# Sheet_1.net
KiCad netlist of a schematic drawn in Altium Designer
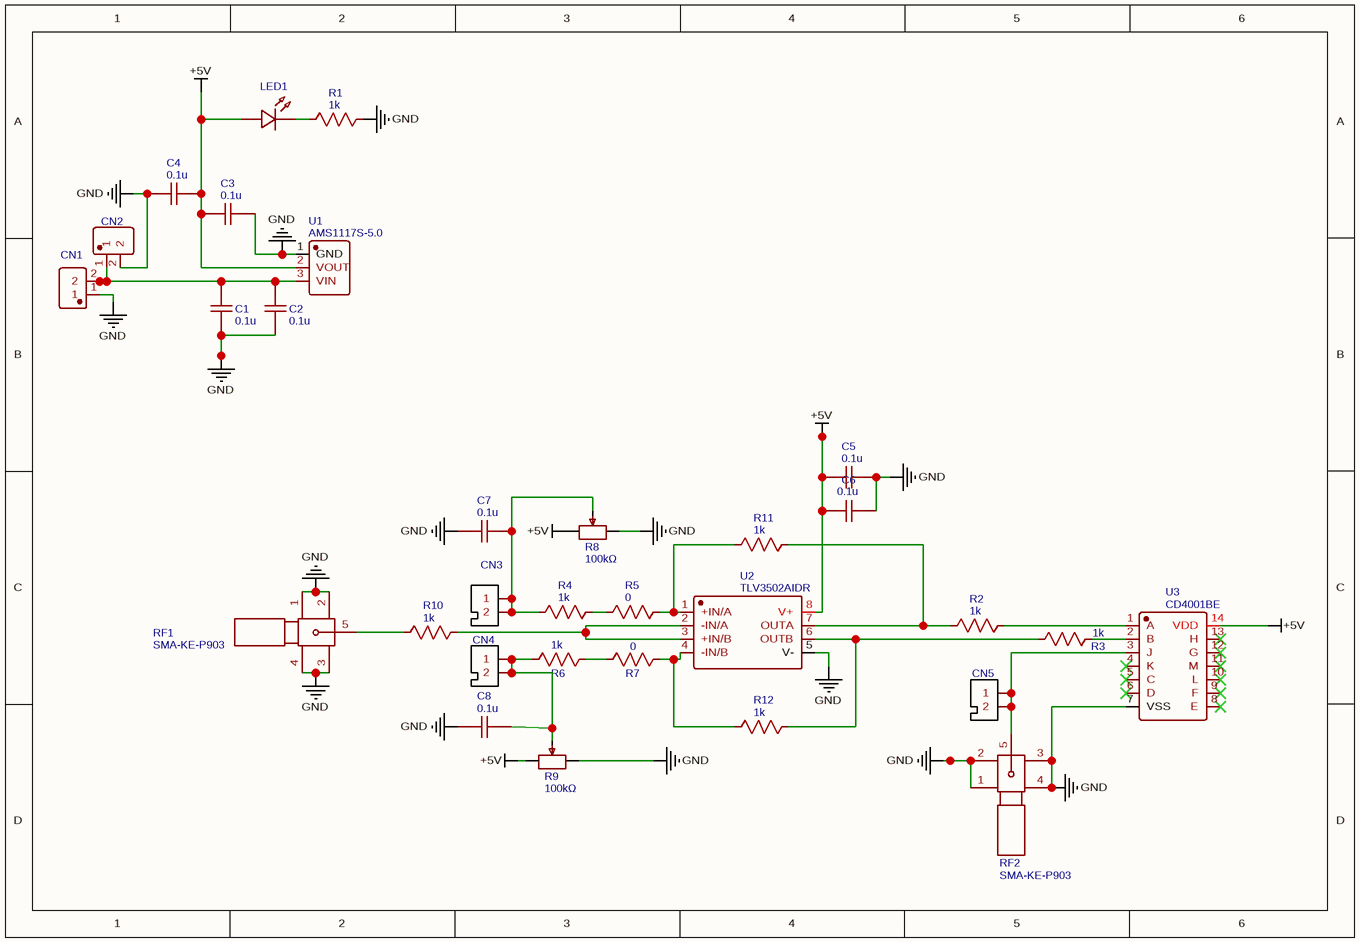
[diagram p0: Sheet_1.schdoc]

(export (version "E")
  (design (tool "Eeschema 10.0.6"))
  (components
    (comp (ref "C1")
      (value "0.1u")
      (fields (field (name "CONTRIBUTOR") "LCEDA_Lib"))
      (libsource (lib "altium-import") (part "root_1_0.1u_"))
    )
    (comp (ref "C2")
      (value "0.1u")
      (fields (field (name "CONTRIBUTOR") "LCEDA_Lib"))
      (libsource (lib "altium-import") (part "root_1_0.1u_"))
    )
    (comp (ref "C3")
      (value "0.1u")
      (fields (field (name "CONTRIBUTOR") "LCEDA_Lib"))
      (libsource (lib "altium-import") (part "root_0_0.1u_"))
    )
    (comp (ref "C4")
      (value "0.1u")
      (fields (field (name "CONTRIBUTOR") "LCEDA_Lib"))
      (libsource (lib "altium-import") (part "root_0_0.1u_"))
    )
    (comp (ref "C5")
      (value "0.1u")
      (fields (field (name "CONTRIBUTOR") "LCEDA_Lib"))
      (libsource (lib "altium-import") (part "root_0_0.1u_"))
    )
    (comp (ref "C6")
      (value "0.1u")
      (fields (field (name "CONTRIBUTOR") "LCEDA_Lib"))
      (libsource (lib "altium-import") (part "root_0_0.1u_"))
    )
    (comp (ref "C7")
      (value "0.1u")
      (fields (field (name "CONTRIBUTOR") "LCEDA_Lib"))
      (libsource (lib "altium-import") (part "root_0_0.1u_"))
    )
    (comp (ref "C8")
      (value "0.1u")
      (fields (field (name "CONTRIBUTOR") "LCEDA_Lib"))
      (libsource (lib "altium-import") (part "root_0_0.1u_"))
    )
    (comp (ref "CN1")
      (value "VH-2A_C722829")
      (fields
        (field (name "BOM_SUPPLIER PART") "C722829")
        (field (name "BOM_MANUFACTURER PART") "VH-2A")
        (field (name "CONTRIBUTOR") "LCSC")
      )
      (libsource (lib "altium-import") (part "root_2_VH-2A_C722829_"))
    )
    (comp (ref "CN2")
      (value "VH-2A_C722829")
      (fields
        (field (name "BOM_SUPPLIER PART") "C722829")
        (field (name "BOM_MANUFACTURER PART") "VH-2A")
        (field (name "CONTRIBUTOR") "LCSC")
      )
      (libsource (lib "altium-import") (part "root_1_VH-2A_C722829_"))
    )
    (comp (ref "CN3")
      (value "A2543WV-2P")
      (fields (field (name "BOM_SUPPLIER PART") "C239362") (field (name "CONTRIBUTOR") "LCSC"))
      (libsource (lib "altium-import") (part "root_2_A2543WV-2P_"))
    )
    (comp (ref "CN4")
      (value "A2543WV-2P")
      (fields (field (name "BOM_SUPPLIER PART") "C239362") (field (name "CONTRIBUTOR") "LCSC"))
      (libsource (lib "altium-import") (part "root_2_A2543WV-2P_"))
    )
    (comp (ref "CN5")
      (value "A2543WV-2P")
      (fields (field (name "BOM_SUPPLIER PART") "C239362") (field (name "CONTRIBUTOR") "LCSC"))
      (libsource (lib "altium-import") (part "root_2_A2543WV-2P_"))
    )
    (comp (ref "LED1")
      (value "LED-0603_R")
      (fields
        (field (name "BOM_MANUFACTURER PART") "19-217/R6C-AL1M2VY/3T")
        (field (name "BOM_SUPPLIER PART") "C72044")
        (field (name "CONTRIBUTOR") "LCEDA_01")
      )
      (libsource (lib "altium-import") (part "root_0_LED-0603_R_"))
    )
    (comp (ref "R1")
      (value "1k")
      (fields (field (name "CONTRIBUTOR") "LCEDA_Lib"))
      (libsource (lib "altium-import") (part "root_0_1k_"))
    )
    (comp (ref "R2")
      (value "1k")
      (fields (field (name "CONTRIBUTOR") "LCEDA_Lib"))
      (libsource (lib "altium-import") (part "root_0_1k_"))
    )
    (comp (ref "R3")
      (value "1k")
      (fields (field (name "CONTRIBUTOR") "LCEDA_Lib"))
      (libsource (lib "altium-import") (part "root_0_1k_"))
    )
    (comp (ref "R4")
      (value "1k")
      (fields (field (name "CONTRIBUTOR") "LCEDA_Lib"))
      (libsource (lib "altium-import") (part "root_0_1k_"))
    )
    (comp (ref "R5")
      (value "0")
      (fields (field (name "CONTRIBUTOR") "LCEDA_Lib"))
      (libsource (lib "altium-import") (part "root_0_0_"))
    )
    (comp (ref "R6")
      (value "1k")
      (fields (field (name "CONTRIBUTOR") "LCEDA_Lib"))
      (libsource (lib "altium-import") (part "root_0_1k_"))
    )
    (comp (ref "R7")
      (value "0")
      (fields (field (name "CONTRIBUTOR") "LCEDA_Lib"))
      (libsource (lib "altium-import") (part "root_0_0_"))
    )
    (comp (ref "R8")
      (value "100kΩ")
      (fields
        (field (name "BOM_MANUFACTURER PART") "3296W-1-104LF")
        (field (name "BOM_SUPPLIER PART") "C48084")
      )
      (libsource (lib "altium-import") (part "root_3_100kΩ_"))
    )
    (comp (ref "R9")
      (value "100kΩ")
      (fields
        (field (name "BOM_MANUFACTURER PART") "3296W-1-104LF")
        (field (name "BOM_SUPPLIER PART") "C48084")
      )
      (libsource (lib "altium-import") (part "root_3_100kΩ_"))
    )
    (comp (ref "R10")
      (value "1k")
      (fields (field (name "CONTRIBUTOR") "LCEDA_Lib"))
      (libsource (lib "altium-import") (part "root_0_1k_"))
    )
    (comp (ref "R11")
      (value "1k")
      (fields (field (name "CONTRIBUTOR") "LCEDA_Lib"))
      (libsource (lib "altium-import") (part "root_0_1k_"))
    )
    (comp (ref "R12")
      (value "1k")
      (fields (field (name "CONTRIBUTOR") "LCEDA_Lib"))
      (libsource (lib "altium-import") (part "root_0_1k_"))
    )
    (comp (ref "RF1")
      (value "SMA-KE-P903")
      (fields (field (name "BOM_SUPPLIER PART") "C914558") (field (name "CONTRIBUTOR") "LCSC"))
      (libsource (lib "altium-import") (part "root_0_SMA-KE-P903_"))
    )
    (comp (ref "RF2")
      (value "SMA-KE-P903")
      (fields (field (name "BOM_SUPPLIER PART") "C914558") (field (name "CONTRIBUTOR") "LCSC"))
      (libsource (lib "altium-import") (part "root_1_SMA-KE-P903_"))
    )
    (comp (ref "U1")
      (value "AMS1117S-5.0")
      (fields
        (field (name "BOM_SUPPLIER PART") "C917182")
        (field (name "SUBPART_NO") "1")
        (field (name "CONTRIBUTOR") "LCSC")
      )
      (libsource (lib "altium-import") (part "root_0_AMS1117S-5.0_"))
    )
    (comp (ref "U2")
      (value "TLV3502AIDR")
      (fields (field (name "BOM_SUPPLIER PART") "C131165") (field (name "CONTRIBUTOR") "LCSC"))
      (libsource (lib "altium-import") (part "root_0_TLV3502AIDR_"))
    )
    (comp (ref "U3")
      (value "CD4001BE")
      (fields (field (name "BOM_SUPPLIER PART") "C5225"))
      (libsource (lib "altium-import") (part "root_0_CD4001BE_"))
    )
  )
  (nets
    (net (code "1") (name "+5V") (class "Default")
      (node (ref "C3") (pin "1") (pinfunction "1_1") (pintype "passive"))
      (node (ref "C4") (pin "2") (pinfunction "2_2") (pintype "passive"))
      (node (ref "C5") (pin "1") (pinfunction "1_1") (pintype "passive"))
      (node (ref "C6") (pin "1") (pinfunction "1_1") (pintype "passive"))
      (node (ref "LED1") (pin "1") (pinfunction "1_1") (pintype "passive"))
      (node (ref "R8") (pin "3") (pinfunction "3_3") (pintype "passive"))
      (node (ref "R9") (pin "3") (pinfunction "3_3") (pintype "passive"))
      (node (ref "U1") (pin "2") (pinfunction "VOUT_2") (pintype "passive"))
      (node (ref "U2") (pin "8") (pinfunction "V+_8") (pintype "passive"))
      (node (ref "U3") (pin "14") (pinfunction "VDD_14") (pintype "passive"))
    )
    (net (code "2") (name "GND") (class "Default")
      (node (ref "C1") (pin "1") (pinfunction "1_1") (pintype "passive"))
      (node (ref "C2") (pin "1") (pinfunction "1_1") (pintype "passive"))
      (node (ref "C3") (pin "2") (pinfunction "2_2") (pintype "passive"))
      (node (ref "C4") (pin "1") (pinfunction "1_1") (pintype "passive"))
      (node (ref "C5") (pin "2") (pinfunction "2_2") (pintype "passive"))
      (node (ref "C6") (pin "2") (pinfunction "2_2") (pintype "passive"))
      (node (ref "C7") (pin "1") (pinfunction "1_1") (pintype "passive"))
      (node (ref "C8") (pin "1") (pinfunction "1_1") (pintype "passive"))
      (node (ref "CN1") (pin "1") (pinfunction "1_1") (pintype "passive"))
      (node (ref "CN2") (pin "2") (pinfunction "2_2") (pintype "passive"))
      (node (ref "R1") (pin "2") (pinfunction "2_2") (pintype "passive"))
      (node (ref "R8") (pin "1") (pinfunction "1_1") (pintype "passive"))
      (node (ref "R9") (pin "1") (pinfunction "1_1") (pintype "passive"))
      (node (ref "RF1") (pin "1") (pinfunction "1_1") (pintype "passive"))
      (node (ref "RF1") (pin "2") (pinfunction "2_2") (pintype "passive"))
      (node (ref "RF1") (pin "3") (pinfunction "3_3") (pintype "passive"))
      (node (ref "RF1") (pin "4") (pinfunction "4_4") (pintype "passive"))
      (node (ref "RF2") (pin "1") (pinfunction "1_1") (pintype "passive"))
      (node (ref "RF2") (pin "2") (pinfunction "2_2") (pintype "passive"))
      (node (ref "RF2") (pin "3") (pinfunction "3_3") (pintype "passive"))
      (node (ref "RF2") (pin "4") (pinfunction "4_4") (pintype "passive"))
      (node (ref "U1") (pin "1") (pinfunction "GND_1") (pintype "passive"))
      (node (ref "U2") (pin "5") (pinfunction "V-_5") (pintype "passive"))
      (node (ref "U3") (pin "7") (pinfunction "VSS_7") (pintype "passive"))
    )
    (net (code "3") (name "Net-(C7-Pad2)") (class "Default")
      (node (ref "C7") (pin "2") (pinfunction "2_2") (pintype "passive"))
      (node (ref "CN3") (pin "1") (pinfunction "1_1") (pintype "passive"))
      (node (ref "CN3") (pin "2") (pinfunction "2_2") (pintype "passive"))
      (node (ref "R4") (pin "1") (pinfunction "1_1") (pintype "passive"))
      (node (ref "R8") (pin "2") (pinfunction "2_2") (pintype "passive"))
    )
    (net (code "4") (name "Net-(C8-Pad2)") (class "Default")
      (node (ref "C8") (pin "2") (pinfunction "2_2") (pintype "passive"))
      (node (ref "CN4") (pin "1") (pinfunction "1_1") (pintype "passive"))
      (node (ref "CN4") (pin "2") (pinfunction "2_2") (pintype "passive"))
      (node (ref "R6") (pin "1") (pinfunction "1_1") (pintype "passive"))
      (node (ref "R9") (pin "2") (pinfunction "2_2") (pintype "passive"))
    )
    (net (code "5") (name "Net-(LED1-Pad2)") (class "Default")
      (node (ref "LED1") (pin "2") (pinfunction "2_2") (pintype "passive"))
      (node (ref "R1") (pin "1") (pinfunction "1_1") (pintype "passive"))
    )
    (net (code "6") (name "Net-(R4-Pad2)") (class "Default")
      (node (ref "R4") (pin "2") (pinfunction "2_2") (pintype "passive"))
      (node (ref "R5") (pin "1") (pinfunction "1_1") (pintype "passive"))
    )
    (net (code "7") (name "Net-(R6-Pad2)") (class "Default")
      (node (ref "R6") (pin "2") (pinfunction "2_2") (pintype "passive"))
      (node (ref "R7") (pin "1") (pinfunction "1_1") (pintype "passive"))
    )
    (net (code "8") (name "Net-(R10-Pad1)") (class "Default")
      (node (ref "R10") (pin "1") (pinfunction "1_1") (pintype "passive"))
      (node (ref "RF1") (pin "5") (pinfunction "5_5") (pintype "passive"))
    )
    (net (code "9") (name "Net-(U1-VIN)") (class "Default")
      (node (ref "C1") (pin "2") (pinfunction "2_2") (pintype "passive"))
      (node (ref "C2") (pin "2") (pinfunction "2_2") (pintype "passive"))
      (node (ref "CN1") (pin "2") (pinfunction "2_2") (pintype "passive"))
      (node (ref "CN2") (pin "1") (pinfunction "1_1") (pintype "passive"))
      (node (ref "U1") (pin "3") (pinfunction "VIN_3") (pintype "passive"))
    )
    (net (code "10") (name "Net-(U2-+IN{slash}A)") (class "Default")
      (node (ref "R11") (pin "1") (pinfunction "1_1") (pintype "passive"))
      (node (ref "R5") (pin "2") (pinfunction "2_2") (pintype "passive"))
      (node (ref "U2") (pin "1") (pinfunction "+IN/A_1") (pintype "passive"))
    )
    (net (code "11") (name "Net-(U2-+IN{slash}B)") (class "Default")
      (node (ref "R10") (pin "2") (pinfunction "2_2") (pintype "passive"))
      (node (ref "U2") (pin "2") (pinfunction "-IN/A_2") (pintype "passive"))
      (node (ref "U2") (pin "3") (pinfunction "+IN/B_3") (pintype "passive"))
    )
    (net (code "12") (name "Net-(U2--IN{slash}B)") (class "Default")
      (node (ref "R12") (pin "1") (pinfunction "1_1") (pintype "passive"))
      (node (ref "R7") (pin "2") (pinfunction "2_2") (pintype "passive"))
      (node (ref "U2") (pin "4") (pinfunction "-IN/B_4") (pintype "passive"))
    )
    (net (code "13") (name "Net-(U2-OUTA)") (class "Default")
      (node (ref "R11") (pin "2") (pinfunction "2_2") (pintype "passive"))
      (node (ref "R2") (pin "1") (pinfunction "1_1") (pintype "passive"))
      (node (ref "U2") (pin "7") (pinfunction "OUTA_7") (pintype "passive"))
    )
    (net (code "14") (name "Net-(U2-OUTB)") (class "Default")
      (node (ref "R12") (pin "2") (pinfunction "2_2") (pintype "passive"))
      (node (ref "R3") (pin "1") (pinfunction "1_1") (pintype "passive"))
      (node (ref "U2") (pin "6") (pinfunction "OUTB_6") (pintype "passive"))
    )
    (net (code "15") (name "Net-(U3-A)") (class "Default")
      (node (ref "R2") (pin "2") (pinfunction "2_2") (pintype "passive"))
      (node (ref "U3") (pin "1") (pinfunction "A_1") (pintype "passive"))
    )
    (net (code "16") (name "Net-(U3-B)") (class "Default")
      (node (ref "R3") (pin "2") (pinfunction "2_2") (pintype "passive"))
      (node (ref "U3") (pin "2") (pinfunction "B_2") (pintype "passive"))
    )
    (net (code "17") (name "Net-(U3-J)") (class "Default")
      (node (ref "CN5") (pin "1") (pinfunction "1_1") (pintype "passive"))
      (node (ref "CN5") (pin "2") (pinfunction "2_2") (pintype "passive"))
      (node (ref "RF2") (pin "5") (pinfunction "5_5") (pintype "passive"))
      (node (ref "U3") (pin "3") (pinfunction "J_3") (pintype "passive"))
    )
    (net (code "18") (name "unconnected-(U3-C-Pad5)") (class "Default")
      (node (ref "U3") (pin "5") (pinfunction "C_5") (pintype "passive+no_connect"))
    )
    (net (code "19") (name "unconnected-(U3-D-Pad6)") (class "Default")
      (node (ref "U3") (pin "6") (pinfunction "D_6") (pintype "passive+no_connect"))
    )
    (net (code "20") (name "unconnected-(U3-E-Pad8)") (class "Default")
      (node (ref "U3") (pin "8") (pinfunction "E_8") (pintype "passive+no_connect"))
    )
    (net (code "21") (name "unconnected-(U3-F-Pad9)") (class "Default")
      (node (ref "U3") (pin "9") (pinfunction "F_9") (pintype "passive+no_connect"))
    )
    (net (code "22") (name "unconnected-(U3-G-Pad12)") (class "Default")
      (node (ref "U3") (pin "12") (pinfunction "G_12") (pintype "passive+no_connect"))
    )
    (net (code "23") (name "unconnected-(U3-H-Pad13)") (class "Default")
      (node (ref "U3") (pin "13") (pinfunction "H_13") (pintype "passive+no_connect"))
    )
    (net (code "24") (name "unconnected-(U3-K-Pad4)") (class "Default")
      (node (ref "U3") (pin "4") (pinfunction "K_4") (pintype "passive+no_connect"))
    )
    (net (code "25") (name "unconnected-(U3-L-Pad10)") (class "Default")
      (node (ref "U3") (pin "10") (pinfunction "L_10") (pintype "passive+no_connect"))
    )
    (net (code "26") (name "unconnected-(U3-M-Pad11)") (class "Default")
      (node (ref "U3") (pin "11") (pinfunction "M_11") (pintype "passive+no_connect"))
    )
  )
)
